# Slave_Relay.net
KiCad netlist of a schematic drawn in Altium Designer
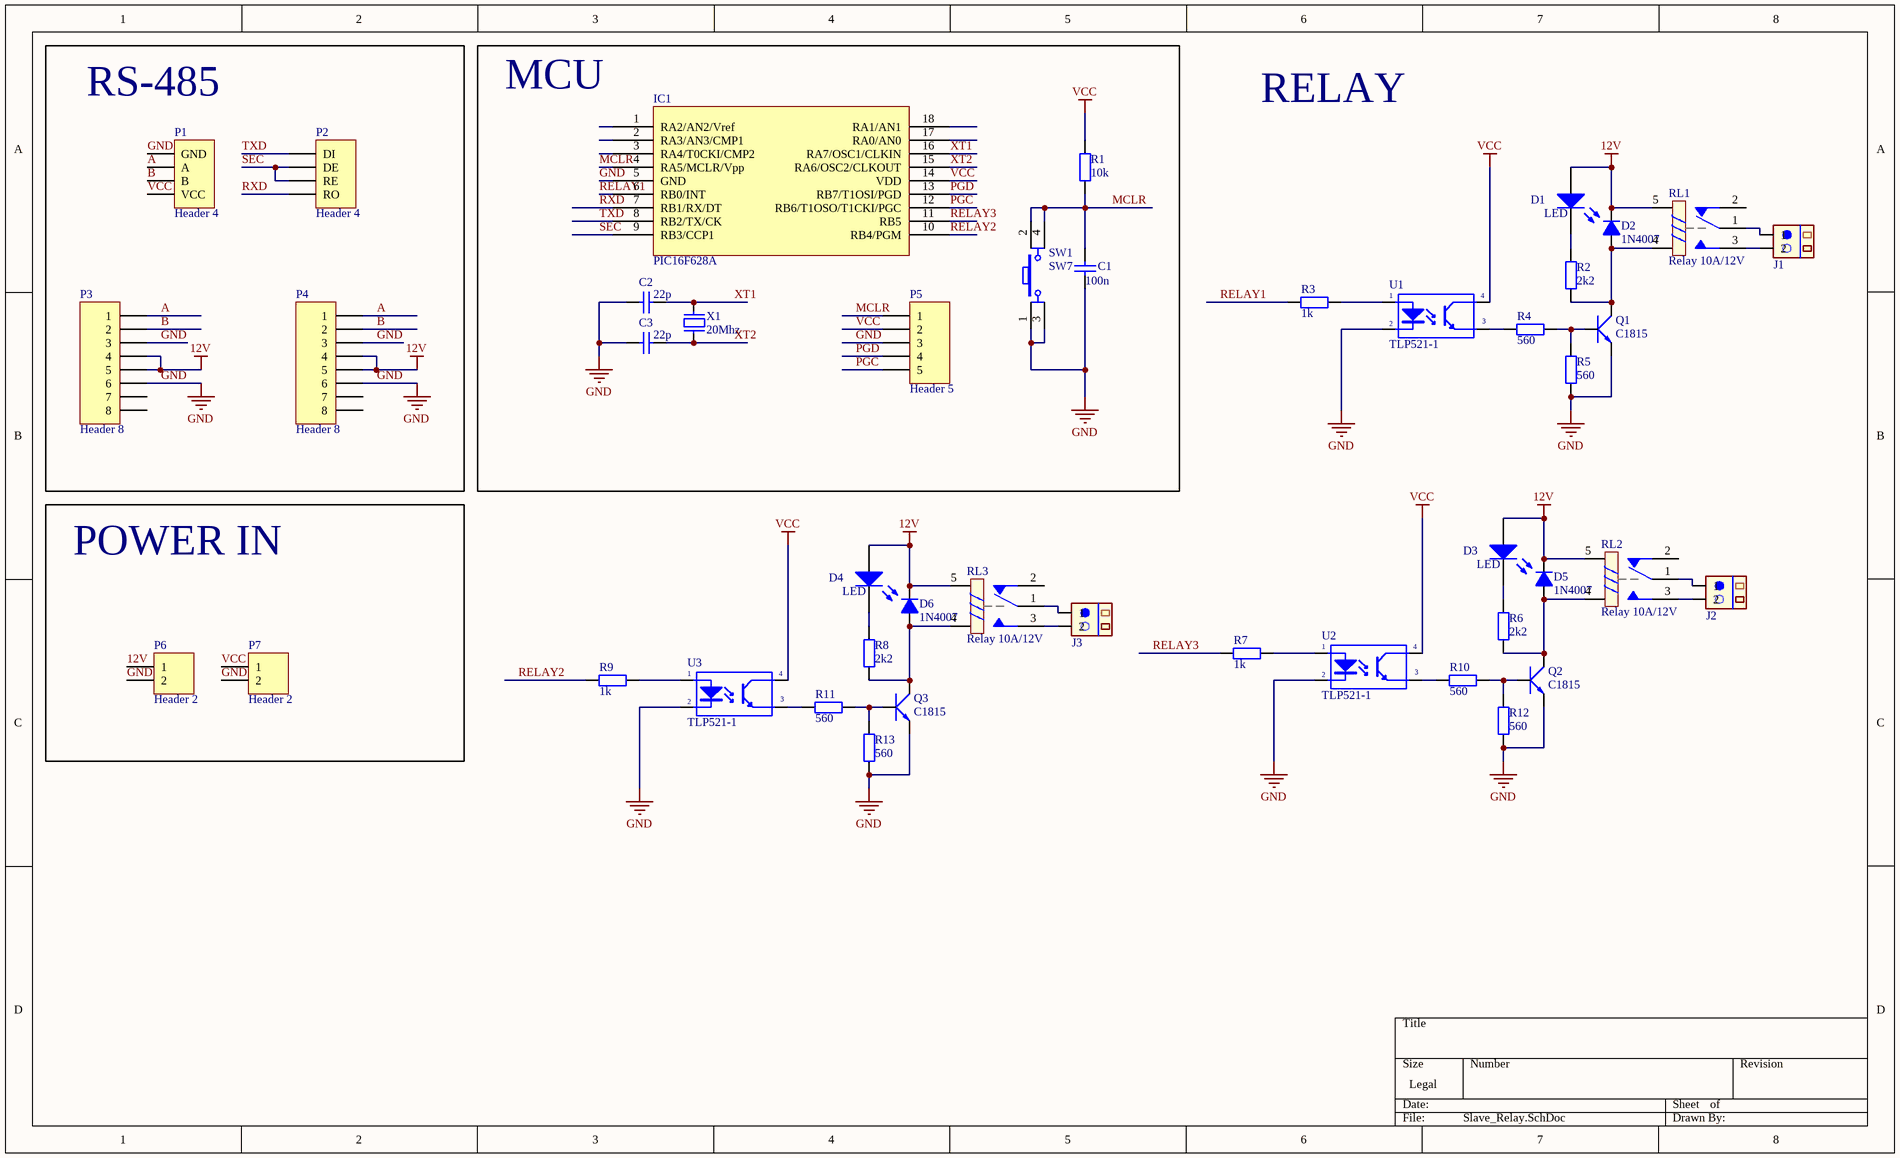
[diagram p0: Slave_Relay.SchDoc]

(export (version "E")
  (design (tool "Eeschema 10.0.6"))
  (components
    (comp (ref "C1")
      (value "100n")
      (footprint "Cap Non-Pol 3mm")
      (description "Capacitor")
      (fields (field (name "Comment") "Capacitor Ceramic") (field (name "PUBLISHER") "Altium Limited"))
      (libsource (lib "THG") (part "CapSMD"))
    )
    (comp (ref "C2")
      (value "22p")
      (footprint "Cap Non-Pol 3mm")
      (description "Non-polarized Capacitor")
      (fields (field (name "Comment") "Cap Non-pol") (field (name "PUBLISHER") "Altium Limited"))
      (libsource (lib "THG") (part "Cap Non-pol"))
    )
    (comp (ref "C3")
      (value "22p")
      (footprint "Cap Non-Pol 3mm")
      (description "Non-polarized Capacitor")
      (fields (field (name "Comment") "Cap Non-pol") (field (name "PUBLISHER") "Altium Limited"))
      (libsource (lib "THG") (part "Cap Non-pol"))
    )
    (comp (ref "D1")
      (value "LED")
      (footprint "LED-0 5mm RED")
      (description "Typical LED")
      (fields (field (name "PUBLISHER") "Altium Limited"))
      (libsource (lib "THG") (part "LED"))
    )
    (comp (ref "D2")
      (value "1N4007")
      (footprint "D1A")
      (description "Diode 1A")
      (libsource (lib "syhaunguyen") (part "D1A"))
    )
    (comp (ref "D3")
      (value "LED")
      (footprint "LED-0 5mm RED")
      (description "Typical LED")
      (fields (field (name "PUBLISHER") "Altium Limited"))
      (libsource (lib "THG") (part "LED"))
    )
    (comp (ref "D4")
      (value "LED")
      (footprint "LED-0 5mm RED")
      (description "Typical LED")
      (fields (field (name "PUBLISHER") "Altium Limited"))
      (libsource (lib "THG") (part "LED"))
    )
    (comp (ref "D5")
      (value "1N4007")
      (footprint "D1A")
      (description "Diode 1A")
      (libsource (lib "syhaunguyen") (part "D1A"))
    )
    (comp (ref "D6")
      (value "1N4007")
      (footprint "D1A")
      (description "Diode 1A")
      (libsource (lib "syhaunguyen") (part "D1A"))
    )
    (comp (ref "IC1")
      (value "PIC16F628A")
      (footprint "DIP18/W0.3")
      (libsource (lib "THG") (part "PIC16F628A"))
    )
    (comp (ref "J1")
      (value "CON.Domino2")
      (footprint "DOMINO 2B")
      (description "2 pins Domino Header")
      (fields (field (name "PUBLISHER") "Hoang Nguyen"))
      (libsource (lib "THG") (part "CON.Domino2"))
    )
    (comp (ref "J2")
      (value "CON.Domino2")
      (footprint "DOMINO 2B")
      (description "2 pins Domino Header")
      (fields (field (name "PUBLISHER") "Hoang Nguyen"))
      (libsource (lib "THG") (part "CON.Domino2"))
    )
    (comp (ref "J3")
      (value "CON.Domino2")
      (footprint "DOMINO 2B")
      (description "2 pins Domino Header")
      (fields (field (name "PUBLISHER") "Hoang Nguyen"))
      (libsource (lib "THG") (part "CON.Domino2"))
    )
    (comp (ref "P1")
      (value "Header 4")
      (footprint "HDR1X4")
      (description "Header, 4-Pin")
      (fields (field (name "PUBLISHER") "Altium Limited"))
      (libsource (lib "Miscellaneous Connectors") (part "Header 4"))
    )
    (comp (ref "P2")
      (value "Header 4")
      (footprint "HDR1X4")
      (description "Header, 4-Pin")
      (fields (field (name "PUBLISHER") "Altium Limited"))
      (libsource (lib "Miscellaneous Connectors") (part "Header 4"))
    )
    (comp (ref "P3")
      (value "Header 8")
      (footprint "RJ11")
      (description "Header, 8-Pin")
      (fields (field (name "PUBLISHER") "Altium Limited"))
      (libsource (lib "THG") (part "Header 8"))
    )
    (comp (ref "P4")
      (value "Header 8")
      (footprint "RJ11")
      (description "Header, 8-Pin")
      (fields (field (name "PUBLISHER") "Altium Limited"))
      (libsource (lib "THG") (part "Header 8"))
    )
    (comp (ref "P5")
      (value "Header 5")
      (footprint "Header 5")
      (description "Header, 5-Pin")
      (fields (field (name "PUBLISHER") "Altium Limited"))
      (libsource (lib "THG") (part "Header 5"))
    )
    (comp (ref "P6")
      (value "Header 2")
      (footprint "HDR1X2")
      (description "Header, 2-Pin")
      (fields (field (name "PUBLISHER") "Altium Limited"))
      (libsource (lib "Miscellaneous Connectors") (part "Header 2"))
    )
    (comp (ref "P7")
      (value "Header 2")
      (footprint "HDR1X2")
      (description "Header, 2-Pin")
      (fields (field (name "PUBLISHER") "Altium Limited"))
      (libsource (lib "Miscellaneous Connectors") (part "Header 2"))
    )
    (comp (ref "Q1")
      (value "C1815")
      (footprint "QTO-92")
      (description "NPN 600mW, ECB")
      (libsource (lib "syhaunguyen") (part "C1815"))
    )
    (comp (ref "Q2")
      (value "C1815")
      (footprint "QTO-92")
      (description "NPN 600mW, ECB")
      (libsource (lib "syhaunguyen") (part "C1815"))
    )
    (comp (ref "Q3")
      (value "C1815")
      (footprint "QTO-92")
      (description "NPN 600mW, ECB")
      (libsource (lib "syhaunguyen") (part "C1815"))
    )
    (comp (ref "R1")
      (value "10k")
      (footprint "RESISTOR 1/4W")
      (description "RES_0805")
      (fields (field (name "Comment") "RES_SMD_0805") (field (name "PUBLISHER") "Altium Limited"))
      (libsource (lib "") (part "RES_SMD_0805_2"))
    )
    (comp (ref "R2")
      (value "2k2")
      (footprint "RESISTOR 1/4W")
      (description "RES_0805")
      (fields (field (name "Comment") "RES_SMD_0805") (field (name "PUBLISHER") "Altium Limited"))
      (libsource (lib "") (part "RES_SMD_0805_1"))
    )
    (comp (ref "R3")
      (value "1k")
      (footprint "RESISTOR 1/4W")
      (description "RES_0805")
      (fields (field (name "Comment") "RES_SMD_0805") (field (name "PUBLISHER") "Altium Limited"))
      (libsource (lib "THG") (part "RES_SMD_0805"))
    )
    (comp (ref "R4")
      (value "560")
      (footprint "RESISTOR 1/4W")
      (description "RES_0805")
      (fields (field (name "Comment") "RES_SMD_0805") (field (name "PUBLISHER") "Altium Limited"))
      (libsource (lib "THG") (part "RES_SMD_0805"))
    )
    (comp (ref "R5")
      (value "560")
      (footprint "RESISTOR 1/4W")
      (description "RES_0805")
      (fields (field (name "Comment") "RES_SMD_0805") (field (name "PUBLISHER") "Altium Limited"))
      (libsource (lib "") (part "RES_SMD_0805_1"))
    )
    (comp (ref "R6")
      (value "2k2")
      (footprint "RESISTOR 1/4W")
      (description "RES_0805")
      (fields (field (name "Comment") "RES_SMD_0805") (field (name "PUBLISHER") "Altium Limited"))
      (libsource (lib "") (part "RES_SMD_0805_1"))
    )
    (comp (ref "R7")
      (value "1k")
      (footprint "RESISTOR 1/4W")
      (description "RES_0805")
      (fields (field (name "Comment") "RES_SMD_0805") (field (name "PUBLISHER") "Altium Limited"))
      (libsource (lib "THG") (part "RES_SMD_0805"))
    )
    (comp (ref "R8")
      (value "2k2")
      (footprint "RESISTOR 1/4W")
      (description "RES_0805")
      (fields (field (name "Comment") "RES_SMD_0805") (field (name "PUBLISHER") "Altium Limited"))
      (libsource (lib "") (part "RES_SMD_0805_1"))
    )
    (comp (ref "R9")
      (value "1k")
      (footprint "RESISTOR 1/4W")
      (description "RES_0805")
      (fields (field (name "Comment") "RES_SMD_0805") (field (name "PUBLISHER") "Altium Limited"))
      (libsource (lib "THG") (part "RES_SMD_0805"))
    )
    (comp (ref "R10")
      (value "560")
      (footprint "RESISTOR 1/4W")
      (description "RES_0805")
      (fields (field (name "Comment") "RES_SMD_0805") (field (name "PUBLISHER") "Altium Limited"))
      (libsource (lib "THG") (part "RES_SMD_0805"))
    )
    (comp (ref "R11")
      (value "560")
      (footprint "RESISTOR 1/4W")
      (description "RES_0805")
      (fields (field (name "Comment") "RES_SMD_0805") (field (name "PUBLISHER") "Altium Limited"))
      (libsource (lib "THG") (part "RES_SMD_0805"))
    )
    (comp (ref "R12")
      (value "560")
      (footprint "RESISTOR 1/4W")
      (description "RES_0805")
      (fields (field (name "Comment") "RES_SMD_0805") (field (name "PUBLISHER") "Altium Limited"))
      (libsource (lib "") (part "RES_SMD_0805_1"))
    )
    (comp (ref "R13")
      (value "560")
      (footprint "RESISTOR 1/4W")
      (description "RES_0805")
      (fields (field (name "Comment") "RES_SMD_0805") (field (name "PUBLISHER") "Altium Limited"))
      (libsource (lib "") (part "RES_SMD_0805_1"))
    )
    (comp (ref "RL1")
      (value "Relay 10A/12V")
      (footprint "RL_SPDT_10A")
      (description "Relay SPDT,10A - 12VDC 5 Pin")
      (libsource (lib "syhaunguyen") (part "Relay 1"))
    )
    (comp (ref "RL2")
      (value "Relay 10A/12V")
      (footprint "RL_SPDT_10A")
      (description "Relay SPDT,10A - 12VDC 5 Pin")
      (libsource (lib "syhaunguyen") (part "Relay 1"))
    )
    (comp (ref "RL3")
      (value "Relay 10A/12V")
      (footprint "RL_SPDT_10A")
      (description "Relay SPDT,10A - 12VDC 5 Pin")
      (libsource (lib "syhaunguyen") (part "Relay 1"))
    )
    (comp (ref "SW1")
      (value "SW7")
      (footprint "SW4")
      (description "Switch button 4 pin")
      (libsource (lib "syhaunguyen") (part "SW4"))
    )
    (comp (ref "U1")
      (value "TLP521-1")
      (footprint "DIP4/W0.3")
      (description "Single Opto")
      (libsource (lib "syhaunguyen") (part "TLP521-1"))
    )
    (comp (ref "U2")
      (value "TLP521-1")
      (footprint "DIP4/W0.3")
      (description "Single Opto")
      (libsource (lib "syhaunguyen") (part "TLP521-1"))
    )
    (comp (ref "U3")
      (value "TLP521-1")
      (footprint "DIP4/W0.3")
      (description "Single Opto")
      (libsource (lib "syhaunguyen") (part "TLP521-1"))
    )
    (comp (ref "X1")
      (value "20Mhz")
      (footprint "XT2")
      (description "Crystal For all Crystal 2pin.")
      (libsource (lib "syhaunguyen") (part "XT2"))
    )
  )
  (nets
    (net (code "1") (name "/A") (class "Default")
      (node (ref "P1") (pin "2") (pinfunction "A_2") (pintype "passive"))
      (node (ref "P3") (pin "1") (pinfunction "1_1") (pintype "passive"))
      (node (ref "P4") (pin "1") (pinfunction "1_1") (pintype "passive"))
    )
    (net (code "2") (name "/B") (class "Default")
      (node (ref "P1") (pin "3") (pinfunction "B_3") (pintype "passive"))
      (node (ref "P3") (pin "2") (pinfunction "2_2") (pintype "passive"))
      (node (ref "P4") (pin "2") (pinfunction "2_2") (pintype "passive"))
    )
    (net (code "3") (name "/MCLR") (class "Default")
      (node (ref "C1") (pin "2") (pinfunction "2_2") (pintype "passive"))
      (node (ref "IC1") (pin "4") (pinfunction "RA5/MCLR/Vpp_4") (pintype "passive"))
      (node (ref "P5") (pin "1") (pinfunction "1_1") (pintype "passive"))
      (node (ref "R1") (pin "1") (pinfunction "1_1") (pintype "passive"))
      (node (ref "SW1") (pin "2") (pintype "passive"))
      (node (ref "SW1") (pin "4") (pintype "passive"))
    )
    (net (code "4") (name "/PGC") (class "Default")
      (node (ref "IC1") (pin "12") (pinfunction "RB6/T1OSO/T1CKI/PGC_12") (pintype "passive"))
      (node (ref "P5") (pin "5") (pinfunction "5_5") (pintype "passive"))
    )
    (net (code "5") (name "/PGD") (class "Default")
      (node (ref "IC1") (pin "13") (pinfunction "RB7/T1OSI/PGD_13") (pintype "passive"))
      (node (ref "P5") (pin "4") (pinfunction "4_4") (pintype "passive"))
    )
    (net (code "6") (name "/RELAY1") (class "Default")
      (node (ref "IC1") (pin "6") (pinfunction "RB0/INT_6") (pintype "passive"))
      (node (ref "R3") (pin "2") (pinfunction "2_2") (pintype "passive"))
    )
    (net (code "7") (name "/RELAY2") (class "Default")
      (node (ref "IC1") (pin "10") (pinfunction "RB4/PGM_10") (pintype "passive"))
      (node (ref "R9") (pin "2") (pinfunction "2_2") (pintype "passive"))
    )
    (net (code "8") (name "/RELAY3") (class "Default")
      (node (ref "IC1") (pin "11") (pinfunction "RB5_11") (pintype "passive"))
      (node (ref "R7") (pin "2") (pinfunction "2_2") (pintype "passive"))
    )
    (net (code "9") (name "/RXD") (class "Default")
      (node (ref "IC1") (pin "7") (pinfunction "RB1/RX/DT_7") (pintype "passive"))
      (node (ref "P2") (pin "4") (pinfunction "VCC_4") (pintype "passive"))
    )
    (net (code "10") (name "/SEC") (class "Default")
      (node (ref "IC1") (pin "9") (pinfunction "RB3/CCP1_9") (pintype "passive"))
      (node (ref "P2") (pin "2") (pinfunction "A_2") (pintype "passive"))
      (node (ref "P2") (pin "3") (pinfunction "B_3") (pintype "passive"))
    )
    (net (code "11") (name "/TXD") (class "Default")
      (node (ref "IC1") (pin "8") (pinfunction "RB2/TX/CK_8") (pintype "passive"))
      (node (ref "P2") (pin "1") (pinfunction "GND_1") (pintype "passive"))
    )
    (net (code "12") (name "/XT1") (class "Default")
      (node (ref "C2") (pin "1") (pinfunction "1_1") (pintype "passive"))
      (node (ref "IC1") (pin "16") (pinfunction "RA7/OSC1/CLKIN_16") (pintype "passive"))
      (node (ref "X1") (pin "2") (pinfunction "2_2") (pintype "passive"))
    )
    (net (code "13") (name "/XT2") (class "Default")
      (node (ref "C3") (pin "1") (pinfunction "1_1") (pintype "passive"))
      (node (ref "IC1") (pin "15") (pinfunction "RA6/OSC2/CLKOUT_15") (pintype "passive"))
      (node (ref "X1") (pin "1") (pinfunction "1_1") (pintype "passive"))
    )
    (net (code "14") (name "12V") (class "Default")
      (node (ref "D1") (pin "1") (pinfunction "A_1") (pintype "passive"))
      (node (ref "D2") (pin "2") (pinfunction "K_2") (pintype "passive"))
      (node (ref "D3") (pin "1") (pinfunction "A_1") (pintype "passive"))
      (node (ref "D4") (pin "1") (pinfunction "A_1") (pintype "passive"))
      (node (ref "D5") (pin "2") (pinfunction "K_2") (pintype "passive"))
      (node (ref "D6") (pin "2") (pinfunction "K_2") (pintype "passive"))
      (node (ref "P3") (pin "4") (pinfunction "4_4") (pintype "passive"))
      (node (ref "P3") (pin "5") (pinfunction "5_5") (pintype "passive"))
      (node (ref "P4") (pin "4") (pinfunction "4_4") (pintype "passive"))
      (node (ref "P4") (pin "5") (pinfunction "5_5") (pintype "passive"))
      (node (ref "P6") (pin "1") (pinfunction "1_1") (pintype "passive"))
      (node (ref "RL1") (pin "5") (pinfunction "5_5") (pintype "passive"))
      (node (ref "RL2") (pin "5") (pinfunction "5_5") (pintype "passive"))
      (node (ref "RL3") (pin "5") (pinfunction "5_5") (pintype "passive"))
    )
    (net (code "15") (name "GND") (class "Default")
      (node (ref "C1") (pin "1") (pinfunction "1_1") (pintype "passive"))
      (node (ref "C2") (pin "2") (pinfunction "2_2") (pintype "passive"))
      (node (ref "C3") (pin "2") (pinfunction "2_2") (pintype "passive"))
      (node (ref "IC1") (pin "5") (pinfunction "GND_5") (pintype "passive"))
      (node (ref "P1") (pin "1") (pinfunction "GND_1") (pintype "passive"))
      (node (ref "P3") (pin "3") (pinfunction "3_3") (pintype "passive"))
      (node (ref "P3") (pin "6") (pinfunction "6_6") (pintype "passive"))
      (node (ref "P4") (pin "3") (pinfunction "3_3") (pintype "passive"))
      (node (ref "P4") (pin "6") (pinfunction "6_6") (pintype "passive"))
      (node (ref "P5") (pin "3") (pinfunction "3_3") (pintype "passive"))
      (node (ref "P6") (pin "2") (pinfunction "2_2") (pintype "passive"))
      (node (ref "P7") (pin "2") (pinfunction "2_2") (pintype "passive"))
      (node (ref "Q1") (pin "1") (pinfunction "E_1") (pintype "passive"))
      (node (ref "Q2") (pin "1") (pinfunction "E_1") (pintype "passive"))
      (node (ref "Q3") (pin "1") (pinfunction "E_1") (pintype "passive"))
      (node (ref "R12") (pin "2") (pinfunction "2_2") (pintype "passive"))
      (node (ref "R13") (pin "2") (pinfunction "2_2") (pintype "passive"))
      (node (ref "R5") (pin "2") (pinfunction "2_2") (pintype "passive"))
      (node (ref "SW1") (pin "1") (pintype "passive"))
      (node (ref "SW1") (pin "3") (pintype "passive"))
      (node (ref "U1") (pin "2") (pinfunction "K_2") (pintype "passive"))
      (node (ref "U2") (pin "2") (pinfunction "K_2") (pintype "passive"))
      (node (ref "U3") (pin "2") (pinfunction "K_2") (pintype "passive"))
    )
    (net (code "16") (name "Net-(D1-K)") (class "Default")
      (node (ref "D1") (pin "2") (pinfunction "K_2") (pintype "passive"))
      (node (ref "R2") (pin "1") (pinfunction "1_1") (pintype "passive"))
    )
    (net (code "17") (name "Net-(D2-A)") (class "Default")
      (node (ref "D2") (pin "1") (pinfunction "A_1") (pintype "passive"))
      (node (ref "Q1") (pin "2") (pinfunction "C_2") (pintype "passive"))
      (node (ref "R2") (pin "2") (pinfunction "2_2") (pintype "passive"))
      (node (ref "RL1") (pin "4") (pinfunction "4_4") (pintype "passive"))
    )
    (net (code "18") (name "Net-(D3-K)") (class "Default")
      (node (ref "D3") (pin "2") (pinfunction "K_2") (pintype "passive"))
      (node (ref "R6") (pin "1") (pinfunction "1_1") (pintype "passive"))
    )
    (net (code "19") (name "Net-(D4-K)") (class "Default")
      (node (ref "D4") (pin "2") (pinfunction "K_2") (pintype "passive"))
      (node (ref "R8") (pin "1") (pinfunction "1_1") (pintype "passive"))
    )
    (net (code "20") (name "Net-(D5-A)") (class "Default")
      (node (ref "D5") (pin "1") (pinfunction "A_1") (pintype "passive"))
      (node (ref "Q2") (pin "2") (pinfunction "C_2") (pintype "passive"))
      (node (ref "R6") (pin "2") (pinfunction "2_2") (pintype "passive"))
      (node (ref "RL2") (pin "4") (pinfunction "4_4") (pintype "passive"))
    )
    (net (code "21") (name "Net-(D6-A)") (class "Default")
      (node (ref "D6") (pin "1") (pinfunction "A_1") (pintype "passive"))
      (node (ref "Q3") (pin "2") (pinfunction "C_2") (pintype "passive"))
      (node (ref "R8") (pin "2") (pinfunction "2_2") (pintype "passive"))
      (node (ref "RL3") (pin "4") (pinfunction "4_4") (pintype "passive"))
    )
    (net (code "22") (name "Net-(J1-Pad1)") (class "Default")
      (node (ref "J1") (pin "1") (pinfunction "1_1") (pintype "passive"))
      (node (ref "RL1") (pin "1") (pinfunction "1_1") (pintype "passive"))
    )
    (net (code "23") (name "Net-(J1-Pad2)") (class "Default")
      (node (ref "J1") (pin "2") (pinfunction "2_2") (pintype "passive"))
      (node (ref "RL1") (pin "3") (pinfunction "3_3") (pintype "passive"))
    )
    (net (code "24") (name "Net-(J2-Pad1)") (class "Default")
      (node (ref "J2") (pin "1") (pinfunction "1_1") (pintype "passive"))
      (node (ref "RL2") (pin "1") (pinfunction "1_1") (pintype "passive"))
    )
    (net (code "25") (name "Net-(J2-Pad2)") (class "Default")
      (node (ref "J2") (pin "2") (pinfunction "2_2") (pintype "passive"))
      (node (ref "RL2") (pin "3") (pinfunction "3_3") (pintype "passive"))
    )
    (net (code "26") (name "Net-(J3-Pad1)") (class "Default")
      (node (ref "J3") (pin "1") (pinfunction "1_1") (pintype "passive"))
      (node (ref "RL3") (pin "1") (pinfunction "1_1") (pintype "passive"))
    )
    (net (code "27") (name "Net-(J3-Pad2)") (class "Default")
      (node (ref "J3") (pin "2") (pinfunction "2_2") (pintype "passive"))
      (node (ref "RL3") (pin "3") (pinfunction "3_3") (pintype "passive"))
    )
    (net (code "28") (name "Net-(Q1-B)") (class "Default")
      (node (ref "Q1") (pin "3") (pinfunction "B_3") (pintype "passive"))
      (node (ref "R4") (pin "1") (pinfunction "1_1") (pintype "passive"))
      (node (ref "R5") (pin "1") (pinfunction "1_1") (pintype "passive"))
    )
    (net (code "29") (name "Net-(Q2-B)") (class "Default")
      (node (ref "Q2") (pin "3") (pinfunction "B_3") (pintype "passive"))
      (node (ref "R10") (pin "1") (pinfunction "1_1") (pintype "passive"))
      (node (ref "R12") (pin "1") (pinfunction "1_1") (pintype "passive"))
    )
    (net (code "30") (name "Net-(Q3-B)") (class "Default")
      (node (ref "Q3") (pin "3") (pinfunction "B_3") (pintype "passive"))
      (node (ref "R11") (pin "1") (pinfunction "1_1") (pintype "passive"))
      (node (ref "R13") (pin "1") (pinfunction "1_1") (pintype "passive"))
    )
    (net (code "31") (name "Net-(U1-A)") (class "Default")
      (node (ref "R3") (pin "1") (pinfunction "1_1") (pintype "passive"))
      (node (ref "U1") (pin "1") (pinfunction "A_1") (pintype "passive"))
    )
    (net (code "32") (name "Net-(U1-E)") (class "Default")
      (node (ref "R4") (pin "2") (pinfunction "2_2") (pintype "passive"))
      (node (ref "U1") (pin "3") (pinfunction "E_3") (pintype "passive"))
    )
    (net (code "33") (name "Net-(U2-A)") (class "Default")
      (node (ref "R7") (pin "1") (pinfunction "1_1") (pintype "passive"))
      (node (ref "U2") (pin "1") (pinfunction "A_1") (pintype "passive"))
    )
    (net (code "34") (name "Net-(U2-E)") (class "Default")
      (node (ref "R10") (pin "2") (pinfunction "2_2") (pintype "passive"))
      (node (ref "U2") (pin "3") (pinfunction "E_3") (pintype "passive"))
    )
    (net (code "35") (name "Net-(U3-A)") (class "Default")
      (node (ref "R9") (pin "1") (pinfunction "1_1") (pintype "passive"))
      (node (ref "U3") (pin "1") (pinfunction "A_1") (pintype "passive"))
    )
    (net (code "36") (name "Net-(U3-E)") (class "Default")
      (node (ref "R11") (pin "2") (pinfunction "2_2") (pintype "passive"))
      (node (ref "U3") (pin "3") (pinfunction "E_3") (pintype "passive"))
    )
    (net (code "37") (name "VCC") (class "Default")
      (node (ref "IC1") (pin "14") (pinfunction "VDD_14") (pintype "passive"))
      (node (ref "P1") (pin "4") (pinfunction "VCC_4") (pintype "passive"))
      (node (ref "P5") (pin "2") (pinfunction "2_2") (pintype "passive"))
      (node (ref "P7") (pin "1") (pinfunction "1_1") (pintype "passive"))
      (node (ref "R1") (pin "2") (pinfunction "2_2") (pintype "passive"))
      (node (ref "U1") (pin "4") (pinfunction "C_4") (pintype "passive"))
      (node (ref "U2") (pin "4") (pinfunction "C_4") (pintype "passive"))
      (node (ref "U3") (pin "4") (pinfunction "C_4") (pintype "passive"))
    )
    (net (code "38") (name "unconnected-(IC1-RA0{slash}AN0-Pad17)") (class "Default")
      (node (ref "IC1") (pin "17") (pinfunction "RA0/AN0_17") (pintype "passive"))
    )
    (net (code "39") (name "unconnected-(IC1-RA1{slash}AN1-Pad18)") (class "Default")
      (node (ref "IC1") (pin "18") (pinfunction "RA1/AN1_18") (pintype "passive"))
    )
    (net (code "40") (name "unconnected-(IC1-RA2{slash}AN2{slash}Vref-Pad1)") (class "Default")
      (node (ref "IC1") (pin "1") (pinfunction "RA2/AN2/Vref_1") (pintype "passive"))
    )
    (net (code "41") (name "unconnected-(IC1-RA3{slash}AN3{slash}CMP1-Pad2)") (class "Default")
      (node (ref "IC1") (pin "2") (pinfunction "RA3/AN3/CMP1_2") (pintype "passive"))
    )
    (net (code "42") (name "unconnected-(IC1-RA4{slash}T0CKI{slash}CMP2-Pad3)") (class "Default")
      (node (ref "IC1") (pin "3") (pinfunction "RA4/T0CKI/CMP2_3") (pintype "passive"))
    )
    (net (code "43") (name "unconnected-(P3-Pad7)") (class "Default")
      (node (ref "P3") (pin "7") (pinfunction "7_7") (pintype "passive"))
    )
    (net (code "44") (name "unconnected-(P3-Pad8)") (class "Default")
      (node (ref "P3") (pin "8") (pinfunction "8_8") (pintype "passive"))
    )
    (net (code "45") (name "unconnected-(P4-Pad7)") (class "Default")
      (node (ref "P4") (pin "7") (pinfunction "7_7") (pintype "passive"))
    )
    (net (code "46") (name "unconnected-(P4-Pad8)") (class "Default")
      (node (ref "P4") (pin "8") (pinfunction "8_8") (pintype "passive"))
    )
    (net (code "47") (name "unconnected-(RL1-Pad2)") (class "Default")
      (node (ref "RL1") (pin "2") (pinfunction "2_2") (pintype "passive"))
    )
    (net (code "48") (name "unconnected-(RL2-Pad2)") (class "Default")
      (node (ref "RL2") (pin "2") (pinfunction "2_2") (pintype "passive"))
    )
    (net (code "49") (name "unconnected-(RL3-Pad2)") (class "Default")
      (node (ref "RL3") (pin "2") (pinfunction "2_2") (pintype "passive"))
    )
  )
)
